# design.net
KiCad netlist of a schematic drawn in Altium Designer
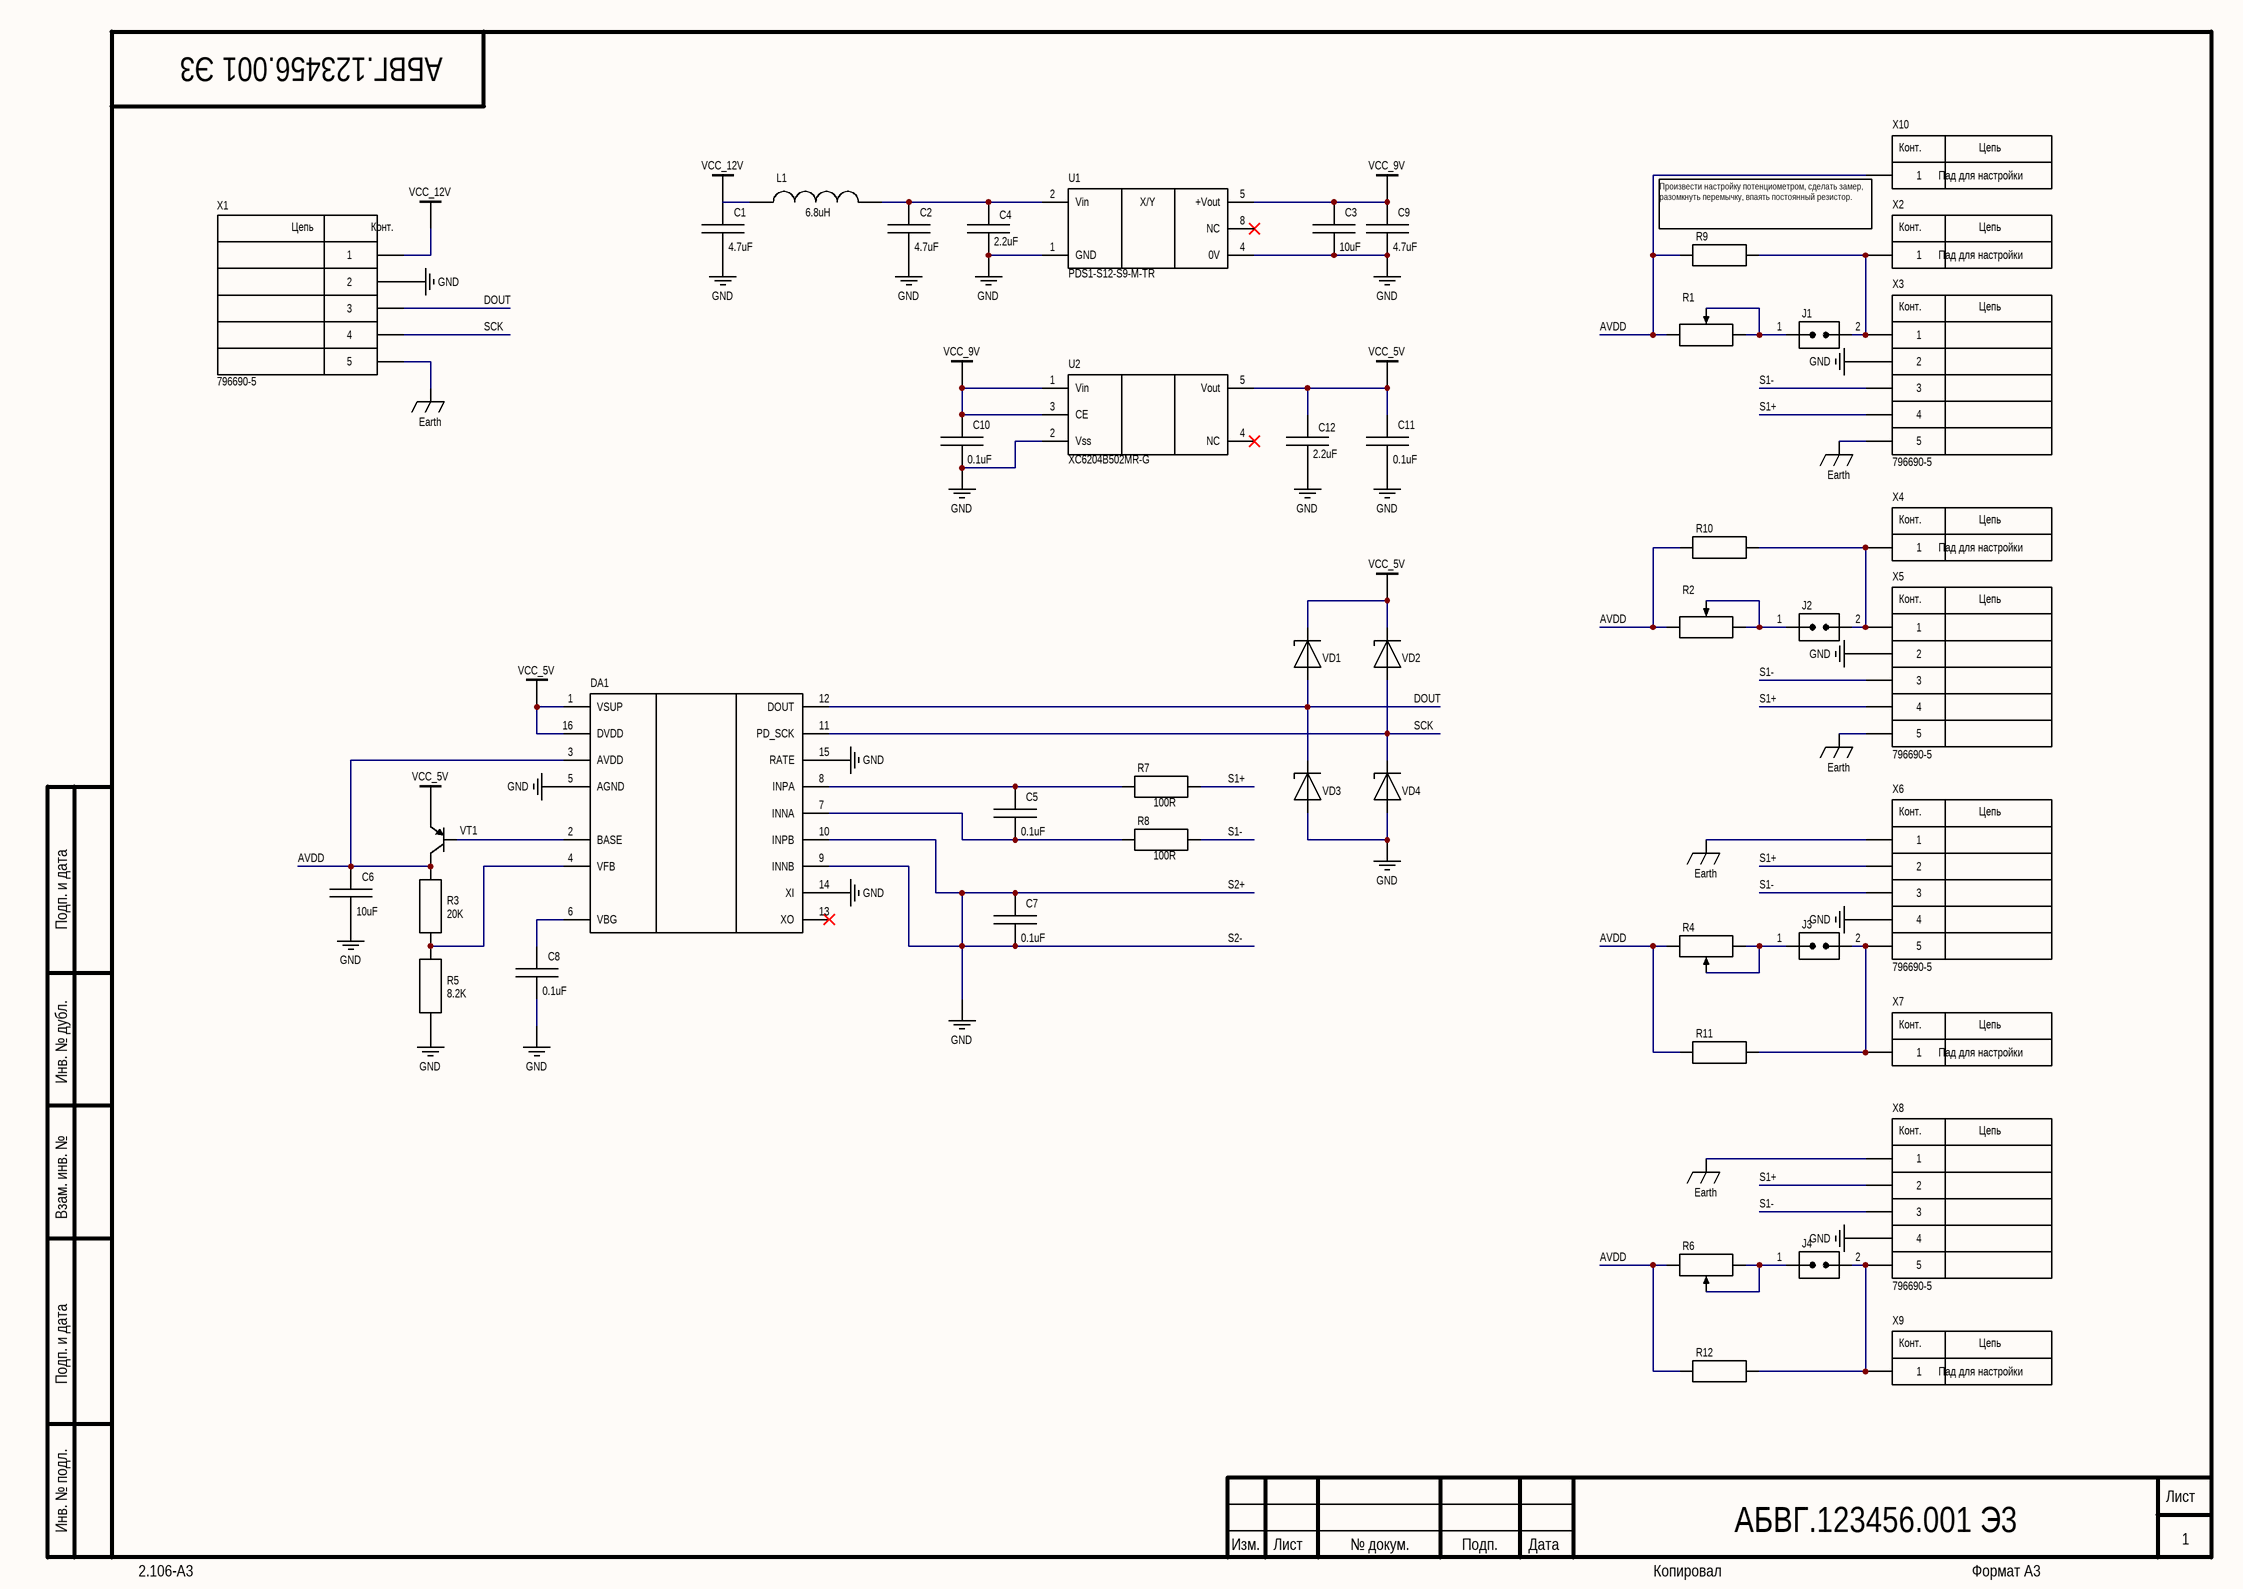
[diagram p0: Схема модуля АЦП.SchDoc]

(export (version "E")
  (design (tool "Eeschema 10.0.6"))
  (components
    (comp (ref "C1")
      (value "4.7uF")
      (footprint "CH0805C")
      (description "4.7 µF ±10% 50V Ceramic Capacitor X5R 0805 (2012 Metric)")
      (fields
        (field (name "MANUFACTURER") "TDK Corporation")
        (field (name "MANUFACTURER PART NUMBER") "C2012X5R1H475K125AB")
      )
      (libsource (lib "Schlib") (part "Capacitor"))
    )
    (comp (ref "C2")
      (value "4.7uF")
      (footprint "CH0805C")
      (description "4.7 µF ±10% 50V Ceramic Capacitor X5R 0805 (2012 Metric)")
      (fields
        (field (name "MANUFACTURER") "TDK Corporation")
        (field (name "MANUFACTURER PART NUMBER") "C2012X5R1H475K125AB")
      )
      (libsource (lib "Schlib") (part "Capacitor"))
    )
    (comp (ref "C3")
      (value "10uF")
      (footprint "CH1206C")
      (description "Cap Ceramic 10uF 16V X7R 20% SMD 1206 125°C Embossed T/R")
      (fields
        (field (name "MANUFACTURER") "Samsung Electro-Mechanics")
        (field (name "MANUFACTURER PART NUMBER") "CL31B106MOHNNNE")
      )
      (libsource (lib "Schlib") (part "Capacitor"))
    )
    (comp (ref "C4")
      (value "2.2uF")
      (footprint "CH1206C")
      (fields (field (name "MANUFACTURER") "Samsung Electro-Mechanics"))
      (libsource (lib "Schlib") (part "Capacitor"))
    )
    (comp (ref "C5")
      (value "0.1uF")
      (footprint "CH0805C")
      (description "Surface Mount Ceramic Multilayer Capacitor 0.1uF 5% X7R 16V 0805 Paper T/R")
      (fields
        (field (name "MANUFACTURER") "YAGEO")
        (field (name "MANUFACTURER PART NUMBER") "CC0805JRX7R7BB104")
      )
      (libsource (lib "Schlib") (part "Capacitor"))
    )
    (comp (ref "C6")
      (value "10uF")
      (footprint "CH1206C")
      (description "Cap Ceramic 10uF 16V X7R 20% SMD 1206 125°C Embossed T/R")
      (fields
        (field (name "MANUFACTURER") "Samsung Electro-Mechanics")
        (field (name "MANUFACTURER PART NUMBER") "CL31B106MOHNNNE")
      )
      (libsource (lib "Schlib") (part "Capacitor"))
    )
    (comp (ref "C7")
      (value "0.1uF")
      (footprint "CH0805C")
      (description "Surface Mount Ceramic Multilayer Capacitor 0.1uF 5% X7R 16V 0805 Paper T/R")
      (fields
        (field (name "MANUFACTURER") "YAGEO")
        (field (name "MANUFACTURER PART NUMBER") "CC0805JRX7R7BB104")
      )
      (libsource (lib "Schlib") (part "Capacitor"))
    )
    (comp (ref "C8")
      (value "0.1uF")
      (footprint "CH0805C")
      (description "Surface Mount Ceramic Multilayer Capacitor 0.1uF 5% X7R 16V 0805 Paper T/R")
      (fields
        (field (name "MANUFACTURER") "YAGEO")
        (field (name "MANUFACTURER PART NUMBER") "CC0805JRX7R7BB104")
      )
      (libsource (lib "Schlib") (part "Capacitor"))
    )
    (comp (ref "C9")
      (value "4.7uF")
      (footprint "CH0805C")
      (description "4.7 µF ±10% 50V Ceramic Capacitor X5R 0805 (2012 Metric)")
      (fields
        (field (name "MANUFACTURER") "TDK Corporation")
        (field (name "MANUFACTURER PART NUMBER") "C2012X5R1H475K125AB")
      )
      (libsource (lib "Schlib") (part "Capacitor"))
    )
    (comp (ref "C10")
      (value "0.1uF")
      (footprint "CH0805C")
      (description "Surface Mount Ceramic Multilayer Capacitor 0.1uF 5% X7R 16V 0805 Paper T/R")
      (fields
        (field (name "MANUFACTURER") "YAGEO")
        (field (name "MANUFACTURER PART NUMBER") "CC0805JRX7R7BB104")
      )
      (libsource (lib "Schlib") (part "Capacitor"))
    )
    (comp (ref "C11")
      (value "0.1uF")
      (footprint "CH0805C")
      (description "Surface Mount Ceramic Multilayer Capacitor 0.1uF 5% X7R 16V 0805 Paper T/R")
      (fields
        (field (name "MANUFACTURER") "YAGEO")
        (field (name "MANUFACTURER PART NUMBER") "CC0805JRX7R7BB104")
      )
      (libsource (lib "Schlib") (part "Capacitor"))
    )
    (comp (ref "C12")
      (value "2.2uF")
      (footprint "CH1206C")
      (fields (field (name "MANUFACTURER") "Samsung Electro-Mechanics"))
      (libsource (lib "Schlib") (part "Capacitor"))
    )
    (comp (ref "DA1")
      (value "HX711")
      (footprint "16-SOP")
      (description "ADC for Weigh Scales")
      (libsource (lib "Schlib") (part "HX711"))
    )
    (comp (ref "J1")
      (value "Jumper-2")
      (footprint "custom:CON: JUMPER_2")
      (description "Jumper")
      (fields (field (name "MANUFACTURER") "China"))
      (libsource (lib "Connectors") (part "Jumper-2"))
    )
    (comp (ref "J2")
      (value "Jumper-2")
      (footprint "custom:CON: JUMPER_2")
      (description "Jumper")
      (fields (field (name "MANUFACTURER") "China"))
      (libsource (lib "Connectors") (part "Jumper-2"))
    )
    (comp (ref "J3")
      (value "Jumper-2")
      (footprint "custom:CON: JUMPER_2")
      (description "Jumper")
      (fields (field (name "MANUFACTURER") "China"))
      (libsource (lib "Connectors") (part "Jumper-2"))
    )
    (comp (ref "J4")
      (value "Jumper-2")
      (footprint "custom:CON: JUMPER_2")
      (description "Jumper")
      (fields (field (name "MANUFACTURER") "China"))
      (libsource (lib "Connectors") (part "Jumper-2"))
    )
    (comp (ref "L1")
      (value "6.8uH")
      (footprint "CH0603L")
      (fields (field (name "MANUFACTURER") "TDK Corporation"))
      (libsource (lib "Schlib") (part "Inductor"))
    )
    (comp (ref "R1")
      (value "50R")
      (footprint "RES: 3296W")
      (description "50 Ohms 0.5W, 1/2W PC Pins Through Hole Trimmer Potentiometer Cermet 25.0 Turn Top Adjustment")
      (fields (field (name "MANUFACTURER") "Bourns Inc."))
      (libsource (lib "Schlib") (part "ADJ resistor"))
    )
    (comp (ref "R2")
      (value "50R")
      (footprint "RES: 3296W")
      (description "50 Ohms 0.5W, 1/2W PC Pins Through Hole Trimmer Potentiometer Cermet 25.0 Turn Top Adjustment")
      (fields (field (name "MANUFACTURER") "Bourns Inc."))
      (libsource (lib "Schlib") (part "ADJ resistor"))
    )
    (comp (ref "R3")
      (value "20K")
      (footprint "CH0603R")
      (fields (field (name "MANUFACTURER") "YAGEO"))
      (libsource (lib "Schlib") (part "Resistor"))
    )
    (comp (ref "R4")
      (value "50R")
      (footprint "RES: 3296W")
      (description "50 Ohms 0.5W, 1/2W PC Pins Through Hole Trimmer Potentiometer Cermet 25.0 Turn Top Adjustment")
      (fields (field (name "MANUFACTURER") "Bourns Inc."))
      (libsource (lib "") (part "ADJ resistor_1"))
    )
    (comp (ref "R5")
      (value "8.2K")
      (footprint "CH0603R")
      (fields (field (name "MANUFACTURER") "YAGEO"))
      (libsource (lib "Schlib") (part "Resistor"))
    )
    (comp (ref "R6")
      (value "50R")
      (footprint "RES: 3296W")
      (description "50 Ohms 0.5W, 1/2W PC Pins Through Hole Trimmer Potentiometer Cermet 25.0 Turn Top Adjustment")
      (fields (field (name "MANUFACTURER") "Bourns Inc."))
      (libsource (lib "") (part "ADJ resistor_1"))
    )
    (comp (ref "R7")
      (value "100R")
      (footprint "CH0603R")
      (description "100 Ohms ±1% 0.1W, 1/10W Chip Resistor 0603 (1608 Metric) Moisture Resistant Thick Film")
      (fields (field (name "MANUFACTURER") "YAGEO"))
      (libsource (lib "") (part "Resistor_1"))
    )
    (comp (ref "R8")
      (value "100R")
      (footprint "CH0603R")
      (description "100 Ohms ±1% 0.1W, 1/10W Chip Resistor 0603 (1608 Metric) Moisture Resistant Thick Film")
      (fields (field (name "MANUFACTURER") "YAGEO"))
      (libsource (lib "") (part "Resistor_1"))
    )
    (comp (ref "R9") (value "*") (footprint "CH0805R") (libsource (lib "") (part "Resistor_1")))
    (comp (ref "R10") (value "*") (footprint "CH0805R") (libsource (lib "") (part "Resistor_1")))
    (comp (ref "R11") (value "*") (footprint "CH0805R") (libsource (lib "") (part "Resistor_1")))
    (comp (ref "R12") (value "*") (footprint "CH0805R") (libsource (lib "") (part "Resistor_1")))
    (comp (ref "U1")
      (value "PDS1-S12-S9-M-TR")
      (footprint "B1205XT-1WR3-TR")
      (description "Isolated Module DC DC Converter 1 Output 9V - - - 111mA 10.8V - 13.2V Input")
      (fields (field (name "MANUFACTURER") "CUI Inc."))
      (libsource (lib "Schlib") (part "PDS1-S12-S9-M-TR"))
    )
    (comp (ref "U2")
      (value "XC6204B502MR-G")
      (footprint "SOT23-5")
      (description "Linear Voltage Regulator IC Positive Fixed 1 Output 150mA SOT-25-5")
      (fields (field (name "MANUFACTURER") "Torex Semiconductor Ltd"))
      (libsource (lib "Schlib") (part "XC6204B502MR-G"))
    )
    (comp (ref "VD1")
      (value "SP3031-01ETG")
      (footprint "SOD-882")
      (description "7.5V (Typ) Clamp 5A (8/20µs) Ipp Tvs Diode Surface Mount SOD-882")
      (fields (field (name "MANUFACTURER") "Littelfuse Inc."))
      (libsource (lib "Schlib") (part "Diod Zener"))
    )
    (comp (ref "VD2")
      (value "SP3031-01ETG")
      (footprint "SOD-882")
      (description "7.5V (Typ) Clamp 5A (8/20µs) Ipp Tvs Diode Surface Mount SOD-882")
      (fields (field (name "MANUFACTURER") "Littelfuse Inc."))
      (libsource (lib "Schlib") (part "Diod Zener"))
    )
    (comp (ref "VD3")
      (value "SP3031-01ETG")
      (footprint "SOD-882")
      (description "7.5V (Typ) Clamp 5A (8/20µs) Ipp Tvs Diode Surface Mount SOD-882")
      (fields (field (name "MANUFACTURER") "Littelfuse Inc."))
      (libsource (lib "Schlib") (part "Diod Zener"))
    )
    (comp (ref "VD4")
      (value "SP3031-01ETG")
      (footprint "SOD-882")
      (description "7.5V (Typ) Clamp 5A (8/20µs) Ipp Tvs Diode Surface Mount SOD-882")
      (fields (field (name "MANUFACTURER") "Littelfuse Inc."))
      (libsource (lib "Schlib") (part "Diod Zener"))
    )
    (comp (ref "VT1")
      (value "MMSS8550-L-TP")
      (footprint "SOT23_132")
      (description "Bipolar")
      (fields (field (name "MANUFACTURER") "Micro Commercial Co"))
      (libsource (lib "Schlib") (part "PNP"))
    )
    (comp (ref "X1")
      (value "796690-5")
      (footprint "CON: 796690-5")
      (fields (field (name "MANUFACTURER") "TE Connectivity AMP Connectors"))
      (libsource (lib "Schlib") (part "5-Connector"))
    )
    (comp (ref "X2")
      (value "*")
      (footprint "CON: PADS 1x1mm")
      (libsource (lib "Schlib") (part "1-Connector"))
    )
    (comp (ref "X3")
      (value "796690-5")
      (footprint "CON: 796690-5")
      (fields (field (name "MANUFACTURER") "TE Connectivity AMP Connectors"))
      (libsource (lib "") (part "5-Connector_1"))
    )
    (comp (ref "X4")
      (value "*")
      (footprint "CON: PADS 1x1mm")
      (libsource (lib "Schlib") (part "1-Connector"))
    )
    (comp (ref "X5")
      (value "796690-5")
      (footprint "CON: 796690-5")
      (fields (field (name "MANUFACTURER") "TE Connectivity AMP Connectors"))
      (libsource (lib "") (part "5-Connector_1"))
    )
    (comp (ref "X6")
      (value "796690-5")
      (footprint "CON: 796690-5")
      (fields (field (name "MANUFACTURER") "TE Connectivity AMP Connectors"))
      (libsource (lib "") (part "5-Connector_1"))
    )
    (comp (ref "X7")
      (value "*")
      (footprint "CON: PADS 1x1mm")
      (libsource (lib "Schlib") (part "1-Connector"))
    )
    (comp (ref "X8")
      (value "796690-5")
      (footprint "CON: 796690-5")
      (fields (field (name "MANUFACTURER") "TE Connectivity AMP Connectors"))
      (libsource (lib "") (part "5-Connector_1"))
    )
    (comp (ref "X9")
      (value "*")
      (footprint "CON: PADS 1x1mm")
      (libsource (lib "Schlib") (part "1-Connector"))
    )
    (comp (ref "X10")
      (value "*")
      (footprint "CON: PADS 1x1mm")
      (libsource (lib "Schlib") (part "1-Connector"))
    )
  )
  (nets
    (net (code "1") (name "/AVDD") (class "Default")
      (node (ref "C6") (pin "1") (pinfunction "1_1") (pintype "passive"))
      (node (ref "DA1") (pin "3") (pinfunction "AVDD_3") (pintype "passive"))
      (node (ref "R1") (pin "1") (pinfunction "1_1") (pintype "passive"))
      (node (ref "R10") (pin "1") (pinfunction "1_1") (pintype "passive"))
      (node (ref "R11") (pin "1") (pinfunction "1_1") (pintype "passive"))
      (node (ref "R12") (pin "1") (pinfunction "1_1") (pintype "passive"))
      (node (ref "R2") (pin "1") (pinfunction "1_1") (pintype "passive"))
      (node (ref "R3") (pin "2") (pinfunction "2_2") (pintype "passive"))
      (node (ref "R4") (pin "1") (pinfunction "1_1") (pintype "passive"))
      (node (ref "R6") (pin "1") (pinfunction "1_1") (pintype "passive"))
      (node (ref "R9") (pin "1") (pinfunction "1_1") (pintype "passive"))
      (node (ref "VT1") (pin "3") (pinfunction "C_3") (pintype "passive"))
      (node (ref "X10") (pin "1") (pinfunction "1______Пад_для_настройки_1") (pintype "passive"))
    )
    (net (code "2") (name "/DOUT") (class "Default")
      (node (ref "DA1") (pin "12") (pinfunction "DOUT_12") (pintype "passive"))
      (node (ref "VD1") (pin "1") (pinfunction "A_1") (pintype "passive"))
      (node (ref "VD3") (pin "2") (pinfunction "C_2") (pintype "passive"))
      (node (ref "X1") (pin "3") (pinfunction "3_3") (pintype "power_in"))
    )
    (net (code "3") (name "/S1+") (class "Default")
      (node (ref "R7") (pin "2") (pinfunction "2_2") (pintype "passive"))
      (node (ref "X3") (pin "4") (pinfunction "4_4") (pintype "power_in"))
      (node (ref "X5") (pin "4") (pinfunction "4_4") (pintype "power_in"))
      (node (ref "X6") (pin "2") (pinfunction "2_2") (pintype "passive"))
      (node (ref "X8") (pin "2") (pinfunction "2_2") (pintype "passive"))
    )
    (net (code "4") (name "/S1-") (class "Default")
      (node (ref "R8") (pin "2") (pinfunction "2_2") (pintype "passive"))
      (node (ref "X3") (pin "3") (pinfunction "3_3") (pintype "power_in"))
      (node (ref "X5") (pin "3") (pinfunction "3_3") (pintype "power_in"))
      (node (ref "X6") (pin "3") (pinfunction "3_3") (pintype "power_in"))
      (node (ref "X8") (pin "3") (pinfunction "3_3") (pintype "power_in"))
    )
    (net (code "5") (name "/SCK") (class "Default")
      (node (ref "DA1") (pin "11") (pinfunction "PD_SCK_11") (pintype "passive"))
      (node (ref "VD2") (pin "1") (pinfunction "A_1") (pintype "passive"))
      (node (ref "VD4") (pin "2") (pinfunction "C_2") (pintype "passive"))
      (node (ref "X1") (pin "4") (pinfunction "4_4") (pintype "power_in"))
    )
    (net (code "6") (name "Earth") (class "Default")
      (node (ref "X1") (pin "5") (pinfunction "5_5") (pintype "power_in"))
      (node (ref "X3") (pin "5") (pinfunction "5_5") (pintype "power_in"))
      (node (ref "X5") (pin "5") (pinfunction "5_5") (pintype "power_in"))
      (node (ref "X6") (pin "1") (pinfunction "1_1") (pintype "passive"))
      (node (ref "X8") (pin "1") (pinfunction "1_1") (pintype "passive"))
    )
    (net (code "7") (name "GND") (class "Default")
      (node (ref "C1") (pin "2") (pinfunction "2_2") (pintype "passive"))
      (node (ref "C10") (pin "2") (pinfunction "2_2") (pintype "passive"))
      (node (ref "C11") (pin "2") (pinfunction "2_2") (pintype "passive"))
      (node (ref "C12") (pin "2") (pinfunction "2_2") (pintype "passive"))
      (node (ref "C2") (pin "2") (pinfunction "2_2") (pintype "passive"))
      (node (ref "C3") (pin "2") (pinfunction "2_2") (pintype "passive"))
      (node (ref "C4") (pin "2") (pinfunction "2_2") (pintype "passive"))
      (node (ref "C6") (pin "2") (pinfunction "2_2") (pintype "passive"))
      (node (ref "C7") (pin "1") (pinfunction "1_1") (pintype "passive"))
      (node (ref "C7") (pin "2") (pinfunction "2_2") (pintype "passive"))
      (node (ref "C8") (pin "2") (pinfunction "2_2") (pintype "passive"))
      (node (ref "C9") (pin "2") (pinfunction "2_2") (pintype "passive"))
      (node (ref "DA1") (pin "10") (pinfunction "INPB_10") (pintype "passive"))
      (node (ref "DA1") (pin "14") (pinfunction "XI_14") (pintype "passive"))
      (node (ref "DA1") (pin "15") (pinfunction "RATE_15") (pintype "passive"))
      (node (ref "DA1") (pin "5") (pinfunction "AGND_5") (pintype "passive"))
      (node (ref "DA1") (pin "9") (pinfunction "INNB_9") (pintype "passive"))
      (node (ref "R5") (pin "1") (pinfunction "1_1") (pintype "passive"))
      (node (ref "U1") (pin "1") (pinfunction "GND_1") (pintype "power_in"))
      (node (ref "U1") (pin "4") (pinfunction "0V_4") (pintype "passive"))
      (node (ref "U2") (pin "2") (pinfunction "Vss_2") (pintype "power_in"))
      (node (ref "VD3") (pin "1") (pinfunction "A_1") (pintype "passive"))
      (node (ref "VD4") (pin "1") (pinfunction "A_1") (pintype "passive"))
      (node (ref "X1") (pin "2") (pinfunction "2_2") (pintype "passive"))
      (node (ref "X3") (pin "2") (pinfunction "2_2") (pintype "passive"))
      (node (ref "X5") (pin "2") (pinfunction "2_2") (pintype "passive"))
      (node (ref "X6") (pin "4") (pinfunction "4_4") (pintype "power_in"))
      (node (ref "X8") (pin "4") (pinfunction "4_4") (pintype "power_in"))
    )
    (net (code "8") (name "Net-(DA1-BASE)") (class "Default")
      (node (ref "DA1") (pin "2") (pinfunction "BASE_2") (pintype "passive"))
      (node (ref "VT1") (pin "1") (pinfunction "B_1") (pintype "passive"))
    )
    (net (code "9") (name "Net-(DA1-INNA)") (class "Default")
      (node (ref "C5") (pin "2") (pinfunction "2_2") (pintype "passive"))
      (node (ref "DA1") (pin "7") (pinfunction "INNA_7") (pintype "passive"))
      (node (ref "R8") (pin "1") (pinfunction "1_1") (pintype "passive"))
    )
    (net (code "10") (name "Net-(DA1-INPA)") (class "Default")
      (node (ref "C5") (pin "1") (pinfunction "1_1") (pintype "passive"))
      (node (ref "DA1") (pin "8") (pinfunction "INPA_8") (pintype "passive"))
      (node (ref "R7") (pin "1") (pinfunction "1_1") (pintype "passive"))
    )
    (net (code "11") (name "Net-(DA1-VBG)") (class "Default")
      (node (ref "C8") (pin "1") (pinfunction "1_1") (pintype "passive"))
      (node (ref "DA1") (pin "6") (pinfunction "VBG_6") (pintype "passive"))
    )
    (net (code "12") (name "Net-(DA1-VFB)") (class "Default")
      (node (ref "DA1") (pin "4") (pinfunction "VFB_4") (pintype "passive"))
      (node (ref "R3") (pin "1") (pinfunction "1_1") (pintype "passive"))
      (node (ref "R5") (pin "2") (pinfunction "2_2") (pintype "passive"))
    )
    (net (code "13") (name "Net-(J1-IN-Pad1)") (class "Default")
      (node (ref "J1") (pin "1") (pinfunction "IN_1") (pintype "passive"))
      (node (ref "R1") (pin "2") (pinfunction "2_2") (pintype "passive"))
      (node (ref "R1") (pin "3") (pinfunction "3_3") (pintype "passive"))
    )
    (net (code "14") (name "Net-(J2-IN-Pad1)") (class "Default")
      (node (ref "J2") (pin "1") (pinfunction "IN_1") (pintype "passive"))
      (node (ref "R2") (pin "2") (pinfunction "2_2") (pintype "passive"))
      (node (ref "R2") (pin "3") (pinfunction "3_3") (pintype "passive"))
    )
    (net (code "15") (name "Net-(J3-IN-Pad1)") (class "Default")
      (node (ref "J3") (pin "1") (pinfunction "IN_1") (pintype "passive"))
      (node (ref "R4") (pin "2") (pinfunction "2_2") (pintype "passive"))
      (node (ref "R4") (pin "3") (pinfunction "3_3") (pintype "passive"))
    )
    (net (code "16") (name "Net-(J4-IN-Pad1)") (class "Default")
      (node (ref "J4") (pin "1") (pinfunction "IN_1") (pintype "passive"))
      (node (ref "R6") (pin "2") (pinfunction "2_2") (pintype "passive"))
      (node (ref "R6") (pin "3") (pinfunction "3_3") (pintype "passive"))
    )
    (net (code "17") (name "Net-(U1-Vin)") (class "Default")
      (node (ref "C2") (pin "1") (pinfunction "1_1") (pintype "passive"))
      (node (ref "C4") (pin "1") (pinfunction "1_1") (pintype "passive"))
      (node (ref "L1") (pin "1") (pinfunction "1_1") (pintype "passive"))
      (node (ref "U1") (pin "2") (pinfunction "Vin_2") (pintype "power_in"))
    )
    (net (code "18") (name "Net-(X2-1______Пад_для_настройки)") (class "Default")
      (node (ref "J1") (pin "2") (pinfunction "IN_2") (pintype "passive"))
      (node (ref "R9") (pin "2") (pinfunction "2_2") (pintype "passive"))
      (node (ref "X2") (pin "1") (pinfunction "1______Пад_для_настройки_1") (pintype "passive"))
      (node (ref "X3") (pin "1") (pinfunction "1_1") (pintype "passive"))
    )
    (net (code "19") (name "Net-(X4-1______Пад_для_настройки)") (class "Default")
      (node (ref "J2") (pin "2") (pinfunction "IN_2") (pintype "passive"))
      (node (ref "R10") (pin "2") (pinfunction "2_2") (pintype "passive"))
      (node (ref "X4") (pin "1") (pinfunction "1______Пад_для_настройки_1") (pintype "passive"))
      (node (ref "X5") (pin "1") (pinfunction "1_1") (pintype "passive"))
    )
    (net (code "20") (name "Net-(X7-1______Пад_для_настройки)") (class "Default")
      (node (ref "J3") (pin "2") (pinfunction "IN_2") (pintype "passive"))
      (node (ref "R11") (pin "2") (pinfunction "2_2") (pintype "passive"))
      (node (ref "X6") (pin "5") (pinfunction "5_5") (pintype "power_in"))
      (node (ref "X7") (pin "1") (pinfunction "1______Пад_для_настройки_1") (pintype "passive"))
    )
    (net (code "21") (name "Net-(X9-1______Пад_для_настройки)") (class "Default")
      (node (ref "J4") (pin "2") (pinfunction "IN_2") (pintype "passive"))
      (node (ref "R12") (pin "2") (pinfunction "2_2") (pintype "passive"))
      (node (ref "X8") (pin "5") (pinfunction "5_5") (pintype "power_in"))
      (node (ref "X9") (pin "1") (pinfunction "1______Пад_для_настройки_1") (pintype "passive"))
    )
    (net (code "22") (name "VCC_5V") (class "Default")
      (node (ref "C11") (pin "1") (pinfunction "1_1") (pintype "passive"))
      (node (ref "C12") (pin "1") (pinfunction "1_1") (pintype "passive"))
      (node (ref "DA1") (pin "1") (pinfunction "VSUP_1") (pintype "passive"))
      (node (ref "DA1") (pin "16") (pinfunction "DVDD_16") (pintype "passive"))
      (node (ref "U2") (pin "5") (pinfunction "Vout_5") (pintype "passive"))
      (node (ref "VD1") (pin "2") (pinfunction "C_2") (pintype "passive"))
      (node (ref "VD2") (pin "2") (pinfunction "C_2") (pintype "passive"))
      (node (ref "VT1") (pin "2") (pinfunction "E_2") (pintype "passive"))
    )
    (net (code "23") (name "VCC_9V") (class "Default")
      (node (ref "C10") (pin "1") (pinfunction "1_1") (pintype "passive"))
      (node (ref "C3") (pin "1") (pinfunction "1_1") (pintype "passive"))
      (node (ref "C9") (pin "1") (pinfunction "1_1") (pintype "passive"))
      (node (ref "U1") (pin "5") (pinfunction "+Vout_5") (pintype "passive"))
      (node (ref "U2") (pin "1") (pinfunction "Vin_1") (pintype "power_in"))
      (node (ref "U2") (pin "3") (pinfunction "CE_3") (pintype "passive"))
    )
    (net (code "24") (name "VCC_12V") (class "Default")
      (node (ref "C1") (pin "1") (pinfunction "1_1") (pintype "passive"))
      (node (ref "L1") (pin "2") (pinfunction "2_2") (pintype "passive"))
      (node (ref "X1") (pin "1") (pinfunction "1_1") (pintype "passive"))
    )
    (net (code "25") (name "unconnected-(DA1-XO-Pad13)") (class "Default")
      (node (ref "DA1") (pin "13") (pinfunction "XO_13") (pintype "passive+no_connect"))
    )
    (net (code "26") (name "unconnected-(U1-NC-Pad8)") (class "Default")
      (node (ref "U1") (pin "8") (pinfunction "NC_8") (pintype "passive+no_connect"))
    )
    (net (code "27") (name "unconnected-(U2-NC-Pad4)") (class "Default")
      (node (ref "U2") (pin "4") (pinfunction "NC_4") (pintype "passive+no_connect"))
    )
  )
)
